# AVRtest.net
KiCad netlist of a schematic drawn in EAGLE
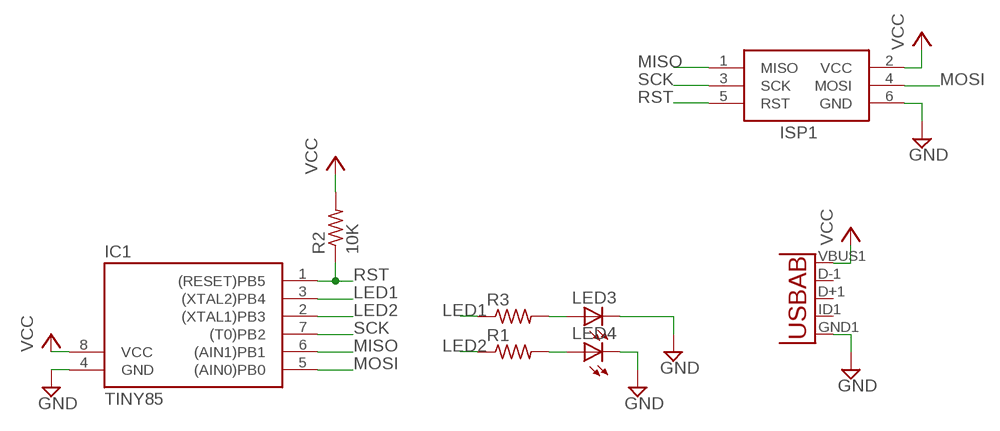
[diagram p0: schematic, sheet 1]

(export (version "E")
  (design (tool "Eeschema 10.0.6"))
  (components
    (comp (ref "IC1")
      (value "TINY85")
      (footprint "eagle-import:SOIC8")
      (libsource (lib "eagle-import") (part "TINY10S"))
    )
    (comp (ref "ISP1")
      (value "AVRISP-6")
      (footprint "eagle-import:AVRISP")
      (libsource (lib "eagle-import") (part "AVRISP-6"))
    )
    (comp (ref "LED3")
      (value "LEDCHIPLED_0805")
      (footprint "eagle-import:CHIPLED_0805")
      (libsource (lib "eagle-import") (part "LEDCHIPLED_0805"))
    )
    (comp (ref "LED4")
      (value "LEDCHIPLED_0805")
      (footprint "eagle-import:CHIPLED_0805")
      (libsource (lib "eagle-import") (part "LEDCHIPLED_0805"))
    )
    (comp (ref "R1")
      (value "R-US_R0805")
      (footprint "eagle-import:R0805")
      (libsource (lib "eagle-import") (part "R-US_R0805"))
    )
    (comp (ref "R2")
      (value "10K")
      (footprint "eagle-import:R0805")
      (libsource (lib "eagle-import") (part "R-US_R0805"))
    )
    (comp (ref "R3")
      (value "R-US_R0805")
      (footprint "eagle-import:R0805")
      (libsource (lib "eagle-import") (part "R-US_R0805"))
    )
    (comp (ref "U1")
      (value "USB\"\"")
      (footprint "eagle-import:USB-MICRO-SMD")
      (libsource (lib "eagle-import") (part "USB{dblquote}{dblquote}"))
    )
  )
  (nets
    (net (code "1") (name "/LED1") (class "Default")
      (node (ref "IC1") (pin "3") (pinfunction "(XTAL2)PB4_3") (pintype "bidirectional"))
      (node (ref "R3") (pin "1") (pinfunction "1_1") (pintype "passive"))
    )
    (net (code "2") (name "/LED2") (class "Default")
      (node (ref "IC1") (pin "2") (pinfunction "(XTAL1)PB3_2") (pintype "bidirectional"))
      (node (ref "R1") (pin "1") (pinfunction "1_1") (pintype "passive"))
    )
    (net (code "3") (name "/MISO") (class "Default")
      (node (ref "IC1") (pin "6") (pinfunction "(AIN1)PB1_6") (pintype "bidirectional"))
      (node (ref "ISP1") (pin "1") (pinfunction "MISO_1") (pintype "input"))
    )
    (net (code "4") (name "/MOSI") (class "Default")
      (node (ref "IC1") (pin "5") (pinfunction "(AIN0)PB0_5") (pintype "bidirectional"))
      (node (ref "ISP1") (pin "4") (pinfunction "MOSI_4") (pintype "output"))
    )
    (net (code "5") (name "/RST") (class "Default")
      (node (ref "IC1") (pin "1") (pinfunction "(RESET)PB5_1") (pintype "bidirectional"))
      (node (ref "ISP1") (pin "5") (pinfunction "RST_5") (pintype "output"))
      (node (ref "R2") (pin "1") (pinfunction "1_1") (pintype "passive"))
    )
    (net (code "6") (name "/SCK") (class "Default")
      (node (ref "IC1") (pin "7") (pinfunction "(T0)PB2_7") (pintype "bidirectional"))
      (node (ref "ISP1") (pin "3") (pinfunction "SCK_3") (pintype "output"))
    )
    (net (code "7") (name "GND") (class "Default")
      (node (ref "IC1") (pin "4") (pinfunction "GND_4") (pintype "power_in"))
      (node (ref "ISP1") (pin "6") (pinfunction "GND_6") (pintype "power_in"))
      (node (ref "LED3") (pin "C") (pinfunction "C_C") (pintype "passive"))
      (node (ref "LED4") (pin "C") (pinfunction "C_C") (pintype "passive"))
      (node (ref "U1") (pin "GND1") (pinfunction "GND_GND1") (pintype "bidirectional"))
    )
    (net (code "8") (name "Net-(LED3-PadA)") (class "Default")
      (node (ref "LED3") (pin "A") (pinfunction "A_A") (pintype "passive"))
      (node (ref "R3") (pin "2") (pinfunction "2_2") (pintype "passive"))
    )
    (net (code "9") (name "Net-(LED4-PadA)") (class "Default")
      (node (ref "LED4") (pin "A") (pinfunction "A_A") (pintype "passive"))
      (node (ref "R1") (pin "2") (pinfunction "2_2") (pintype "passive"))
    )
    (net (code "10") (name "VCC") (class "Default")
      (node (ref "IC1") (pin "8") (pinfunction "VCC_8") (pintype "power_in"))
      (node (ref "ISP1") (pin "2") (pinfunction "VCC_2") (pintype "power_in"))
      (node (ref "R2") (pin "2") (pinfunction "2_2") (pintype "passive"))
      (node (ref "U1") (pin "VBUS1") (pinfunction "VBUS_VBUS1") (pintype "bidirectional"))
    )
    (net (code "11") (name "unconnected-(U1-D+-PadD+1)") (class "Default")
      (node (ref "U1") (pin "D+1") (pinfunction "D+_D+1") (pintype "bidirectional"))
    )
    (net (code "12") (name "unconnected-(U1-D--PadD-1)") (class "Default")
      (node (ref "U1") (pin "D-1") (pinfunction "D-_D-1") (pintype "bidirectional"))
    )
    (net (code "13") (name "unconnected-(U1-USBID-PadID1)") (class "Default")
      (node (ref "U1") (pin "ID1") (pinfunction "USBID_ID1") (pintype "bidirectional"))
    )
  )
)
